# Main.net
KiCad netlist of a schematic drawn in Altium Designer
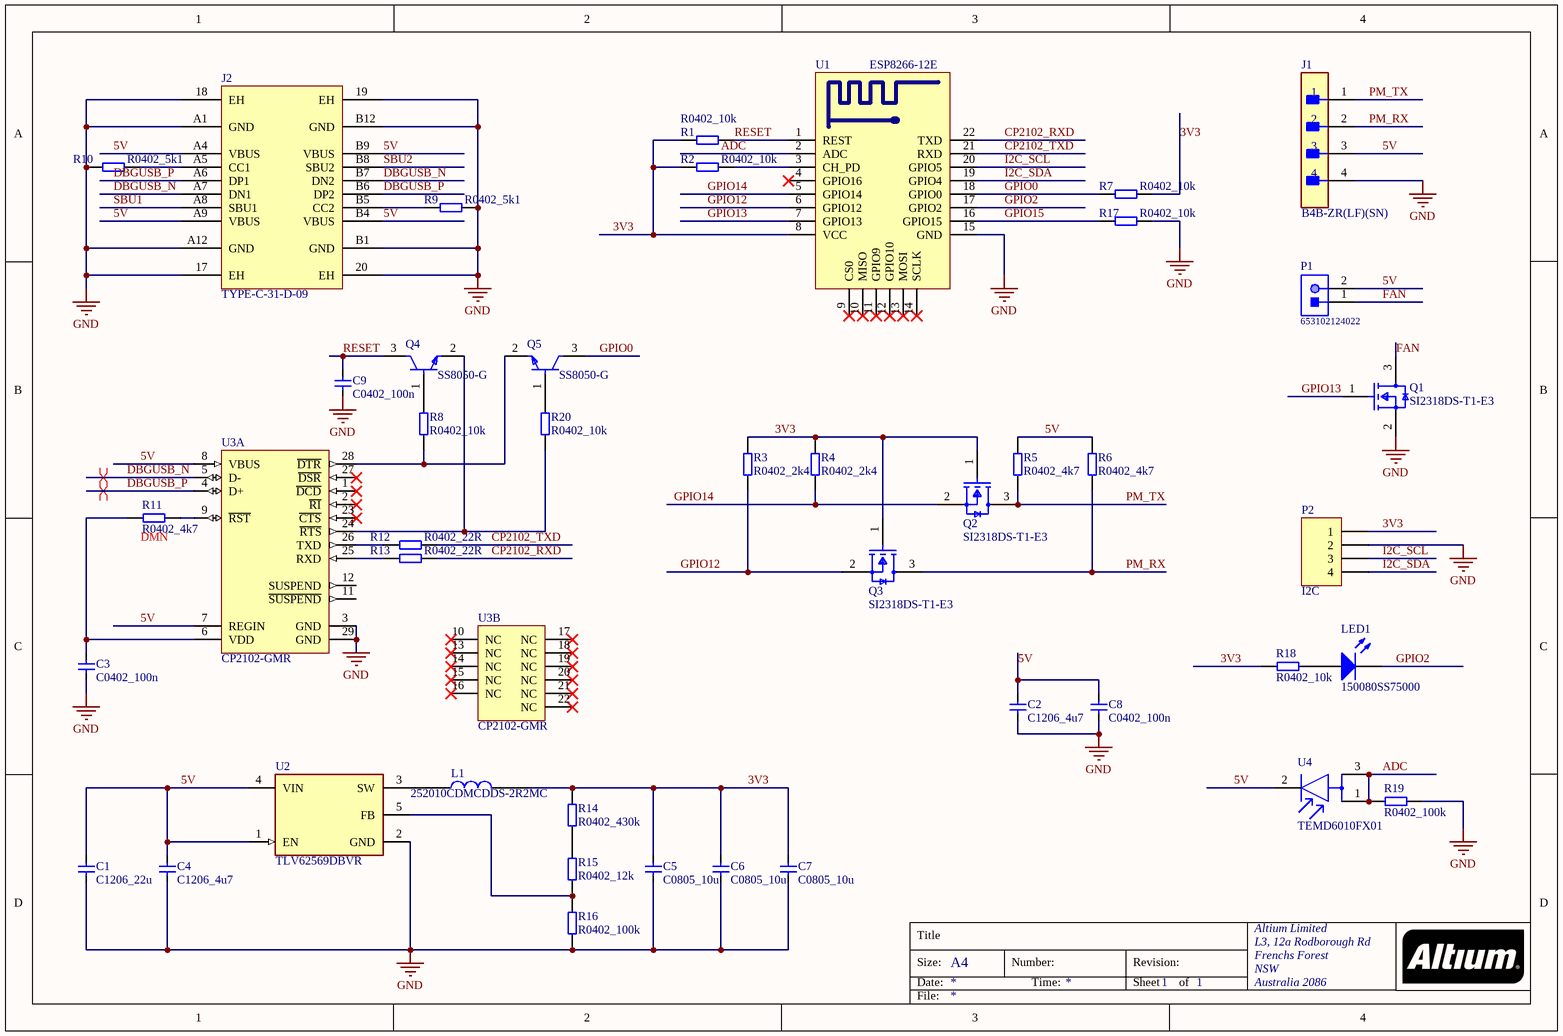
[diagram p0: Main.SchDoc]

(export (version "E")
  (design (tool "Eeschema 10.0.6"))
  (components
    (comp (ref "C1")
      (value "C1206_22u")
      (footprint "C1206")
      (fields (field (name "TOLERANCE") "0.2%"))
      (libsource (lib "NyaMoe Internal Altium Server") (part "Cap"))
    )
    (comp (ref "C2")
      (value "C1206_4u7")
      (footprint "C1206")
      (fields (field (name "TOLERANCE") "0.1%"))
      (libsource (lib "NyaMoe Internal Altium Server") (part "Cap"))
    )
    (comp (ref "C3")
      (value "C0402_100n")
      (footprint "C0402")
      (fields (field (name "TOLERANCE") "0.1%"))
      (libsource (lib "NyaMoe Internal Altium Server") (part "Cap"))
    )
    (comp (ref "C4")
      (value "C1206_4u7")
      (footprint "C1206")
      (fields (field (name "TOLERANCE") "0.1%"))
      (libsource (lib "NyaMoe Internal Altium Server") (part "Cap"))
    )
    (comp (ref "C5")
      (value "C0805_10u")
      (footprint "C0805")
      (description "C0805")
      (fields (field (name "TOLERANCE") "0.05%"))
      (libsource (lib "NyaMoe Internal Altium Server") (part "Cap"))
    )
    (comp (ref "C6")
      (value "C0805_10u")
      (footprint "C0805")
      (description "C0805")
      (fields (field (name "TOLERANCE") "0.05%"))
      (libsource (lib "NyaMoe Internal Altium Server") (part "Cap"))
    )
    (comp (ref "C7")
      (value "C0805_10u")
      (footprint "C0805")
      (description "C0805")
      (fields (field (name "TOLERANCE") "0.05%"))
      (libsource (lib "NyaMoe Internal Altium Server") (part "Cap"))
    )
    (comp (ref "C8")
      (value "C0402_100n")
      (footprint "C0402")
      (fields (field (name "TOLERANCE") "0.1%"))
      (libsource (lib "NyaMoe Internal Altium Server") (part "Cap"))
    )
    (comp (ref "C9")
      (value "C0402_100n")
      (footprint "C0402")
      (fields (field (name "TOLERANCE") "0.1%"))
      (libsource (lib "NyaMoe Internal Altium Server") (part "Cap"))
    )
    (comp (ref "J1")
      (value "B4B-ZR(LF)(SN)")
      (footprint "FP-B4B-ZR_LF_SN-MFG")
      (description "CONN HEADER VERT 4POS 1.5MM")
      (libsource (lib "Altium Content Vault") (part "299a8cea1bdcbc3624fe62c390fa72c"))
    )
    (comp (ref "J2")
      (value "TYPE-C-31-D-09")
      (footprint "New footprint 1")
      (libsource (lib "NyaMoe Internal Altium Server") (part "TYPE-C-31-D-09"))
    )
    (comp (ref "L1")
      (value "252010CDMCDDS-2R2MC")
      (footprint "INDC2520X10N")
      (description "Fixed Ind 2.2UH 2.5A 97 Mohm SMD")
      (libsource (lib "NyaMoe Internal Altium Server") (part "252010CDMCDDS-2R2MC"))
    )
    (comp (ref "LED1")
      (value "150080SS75000")
      (footprint "0805_A")
      (description "SMD mono-color Chip LED, WL-SMCW, Super Red")
      (fields (field (name "MANUFACTURER") "Wuerth Elektronik"))
      (libsource (lib "Altium Content Vault") (part "WE-LED_K1A2-2"))
    )
    (comp (ref "P1")
      (value "653102124022")
      (footprint "653102124022")
      (description "Male Shrouded Header WR-WTB, SMT, Vertical, pitch 1.25 mm, 1 x 2 position")
      (fields (field (name "MANUFACTURER") "Wurth Elektronik") (field (name "PUBLISHER") "WurthElektronik"))
      (libsource (lib "Altium Content Vault") (part "WE-CN-1P-M-R2"))
    )
    (comp (ref "P2")
      (value "I2C")
      (footprint "HDR1X4")
      (description "Header, 4-Pin")
      (fields (field (name "PUBLISHER") "Altium Limited"))
      (libsource (lib "Miscellaneous Connectors") (part "Header 4"))
    )
    (comp (ref "Q1")
      (value "SI2318DS-T1-E3")
      (footprint "FP-S-03946-MFG")
      (description "MOSFET N-CH 40V 3A SOT23-3")
      (fields
        (field (name "MANUFACTURER") "Vishay")
        (field (name "OCTOPART") "https://octopart.com/si2318ds-t1-e3-vishay-40866469")
      )
      (libsource (lib "Altium Content Vault") (part "3b9c635fedb024a5347a57b145af9cc"))
    )
    (comp (ref "Q2")
      (value "SI2318DS-T1-E3")
      (footprint "FP-S-03946-MFG")
      (description "MOSFET N-CH 40V 3A SOT23-3")
      (fields
        (field (name "MANUFACTURER") "Vishay")
        (field (name "OCTOPART") "https://octopart.com/si2318ds-t1-e3-vishay-40866469")
      )
      (libsource (lib "Altium Content Vault") (part "3b9c635fedb024a5347a57b145af9cc"))
    )
    (comp (ref "Q3")
      (value "SI2318DS-T1-E3")
      (footprint "FP-S-03946-MFG")
      (description "MOSFET N-CH 40V 3A SOT23-3")
      (fields
        (field (name "MANUFACTURER") "Vishay")
        (field (name "OCTOPART") "https://octopart.com/si2318ds-t1-e3-vishay-40866469")
      )
      (libsource (lib "Altium Content Vault") (part "3b9c635fedb024a5347a57b145af9cc"))
    )
    (comp (ref "Q4")
      (value "SS8050-G")
      (footprint "FP-SS8050-G-MFG")
      (description "NPN TRANSISTOR 1.5A 40V SOT-23 R")
      (libsource (lib "Altium Content Vault") (part "2a1388f82443b098dcd57d24ac7632d"))
    )
    (comp (ref "Q5")
      (value "SS8050-G")
      (footprint "FP-SS8050-G-MFG")
      (description "NPN TRANSISTOR 1.5A 40V SOT-23 R")
      (libsource (lib "Altium Content Vault") (part "2a1388f82443b098dcd57d24ac7632d"))
    )
    (comp (ref "R1")
      (value "R0402_10k")
      (footprint "R0402")
      (fields (field (name "TOLERANCE") "1%"))
      (libsource (lib "NyaMoe Internal Altium Server") (part "Res"))
    )
    (comp (ref "R2")
      (value "R0402_10k")
      (footprint "R0402")
      (fields (field (name "TOLERANCE") "1%"))
      (libsource (lib "NyaMoe Internal Altium Server") (part "Res"))
    )
    (comp (ref "R3")
      (value "R0402_2k4")
      (footprint "R0402")
      (fields (field (name "TOLERANCE") "1%"))
      (libsource (lib "NyaMoe Internal Altium Server") (part "Res"))
    )
    (comp (ref "R4")
      (value "R0402_2k4")
      (footprint "R0402")
      (fields (field (name "TOLERANCE") "1%"))
      (libsource (lib "NyaMoe Internal Altium Server") (part "Res"))
    )
    (comp (ref "R5")
      (value "R0402_4k7")
      (footprint "R0402")
      (fields (field (name "TOLERANCE") "1%"))
      (libsource (lib "NyaMoe Internal Altium Server") (part "Res"))
    )
    (comp (ref "R6")
      (value "R0402_4k7")
      (footprint "R0402")
      (fields (field (name "TOLERANCE") "1%"))
      (libsource (lib "NyaMoe Internal Altium Server") (part "Res"))
    )
    (comp (ref "R7")
      (value "R0402_10k")
      (footprint "R0402")
      (fields (field (name "TOLERANCE") "1%"))
      (libsource (lib "NyaMoe Internal Altium Server") (part "Res"))
    )
    (comp (ref "R8")
      (value "R0402_10k")
      (footprint "R0402")
      (fields (field (name "TOLERANCE") "1%"))
      (libsource (lib "NyaMoe Internal Altium Server") (part "Res"))
    )
    (comp (ref "R9")
      (value "R0402_5k1")
      (footprint "R0402")
      (fields (field (name "TOLERANCE") "1%"))
      (libsource (lib "NyaMoe Internal Altium Server") (part "Res"))
    )
    (comp (ref "R10")
      (value "R0402_5k1")
      (footprint "R0402")
      (fields (field (name "TOLERANCE") "1%"))
      (libsource (lib "NyaMoe Internal Altium Server") (part "Res"))
    )
    (comp (ref "R11")
      (value "R0402_4k7")
      (footprint "R0402")
      (fields (field (name "TOLERANCE") "1%"))
      (libsource (lib "NyaMoe Internal Altium Server") (part "Res"))
    )
    (comp (ref "R12")
      (value "R0402_22R")
      (footprint "R0402")
      (fields (field (name "TOLERANCE") "1%"))
      (libsource (lib "NyaMoe Internal Altium Server") (part "Res"))
    )
    (comp (ref "R13")
      (value "R0402_22R")
      (footprint "R0402")
      (fields (field (name "TOLERANCE") "1%"))
      (libsource (lib "NyaMoe Internal Altium Server") (part "Res"))
    )
    (comp (ref "R14")
      (value "R0402_430k")
      (footprint "R0402")
      (fields (field (name "TOLERANCE") "1%"))
      (libsource (lib "NyaMoe Internal Altium Server") (part "Res"))
    )
    (comp (ref "R15")
      (value "R0402_12k")
      (footprint "R0402")
      (fields (field (name "TOLERANCE") "1%"))
      (libsource (lib "NyaMoe Internal Altium Server") (part "Res"))
    )
    (comp (ref "R16")
      (value "R0402_100k")
      (footprint "R0402")
      (fields (field (name "TOLERANCE") "1%"))
      (libsource (lib "NyaMoe Internal Altium Server") (part "Res"))
    )
    (comp (ref "R17")
      (value "R0402_10k")
      (footprint "R0402")
      (fields (field (name "TOLERANCE") "1%"))
      (libsource (lib "NyaMoe Internal Altium Server") (part "Res"))
    )
    (comp (ref "R18")
      (value "R0402_10k")
      (footprint "R0402")
      (fields (field (name "TOLERANCE") "1%"))
      (libsource (lib "NyaMoe Internal Altium Server") (part "Res"))
    )
    (comp (ref "R19")
      (value "R0402_100k")
      (footprint "R0402")
      (fields (field (name "TOLERANCE") "1%"))
      (libsource (lib "NyaMoe Internal Altium Server") (part "Res"))
    )
    (comp (ref "R20")
      (value "R0402_10k")
      (footprint "R0402")
      (fields (field (name "TOLERANCE") "1%"))
      (libsource (lib "NyaMoe Internal Altium Server") (part "Res"))
    )
    (comp (ref "U1")
      (value "ESP8266-12E")
      (footprint "ESP_12E")
      (description "串口 WIFI模块，ESP-12E")
      (fields (field (name "版权归属") "源创客"))
      (libsource (lib "13.1 - 模块") (part "ESP8266-12E"))
    )
    (comp (ref "U2")
      (value "TLV62569DBVR")
      (footprint "FP-DBV0005A-MFG")
      (description "IC REG BUCK ADJ 2A SOT23-5")
      (libsource (lib "Altium Content Vault") (part "f8671745ee5fb9a493b385c735b730b"))
    )
    (comp (ref "U3")
      (value "CP2102-GMR")
      (footprint "SLAB-QFN-28-3125x3125TP_M")
      (description "Single-Chip USB to URAT Bridge, 3.3 V, -40 to 85 degC, 28-Pin QFN, RoHS, Tape and Reel")
      (fields (field (name "MANUFACTURER") "Silicon Labs"))
      (libsource (lib "Altium Content Vault") (part "SLAB-CP210X-QFN-28-29"))
    )
    (comp (ref "U4")
      (value "TEMD6010FX01")
      (footprint "FP-6_541-5080_01-4-MFG")
      (description "SENSOR PHOTODIODE 540NM SMD")
      (libsource (lib "Altium Content Vault") (part "efd04f4de317bbfa1bd732263da52e9"))
    )
  )
  (nets
    (net (code "1") (name "/3V3") (class "Default")
      (node (ref "C5") (pin "1") (pinfunction "1_1") (pintype "passive"))
      (node (ref "C6") (pin "1") (pinfunction "1_1") (pintype "passive"))
      (node (ref "C7") (pin "1") (pinfunction "1_1") (pintype "passive"))
      (node (ref "L1") (pin "2") (pinfunction "2_2") (pintype "passive"))
      (node (ref "P2") (pin "1") (pinfunction "1_1") (pintype "passive"))
      (node (ref "Q2") (pin "1") (pinfunction "G_1") (pintype "passive"))
      (node (ref "Q3") (pin "1") (pinfunction "G_1") (pintype "passive"))
      (node (ref "R1") (pin "1") (pinfunction "1_1") (pintype "passive"))
      (node (ref "R14") (pin "2") (pinfunction "2_2") (pintype "passive"))
      (node (ref "R18") (pin "1") (pinfunction "1_1") (pintype "passive"))
      (node (ref "R2") (pin "1") (pinfunction "1_1") (pintype "passive"))
      (node (ref "R3") (pin "2") (pinfunction "2_2") (pintype "passive"))
      (node (ref "R4") (pin "2") (pinfunction "2_2") (pintype "passive"))
      (node (ref "R7") (pin "2") (pinfunction "2_2") (pintype "passive"))
      (node (ref "U1") (pin "8") (pinfunction "VCC_8") (pintype "passive"))
    )
    (net (code "2") (name "/5V") (class "Default")
      (node (ref "C1") (pin "1") (pinfunction "1_1") (pintype "passive"))
      (node (ref "C2") (pin "1") (pinfunction "1_1") (pintype "passive"))
      (node (ref "C4") (pin "1") (pinfunction "1_1") (pintype "passive"))
      (node (ref "C8") (pin "1") (pinfunction "1_1") (pintype "passive"))
      (node (ref "J1") (pin "3") (pinfunction "3_3") (pintype "passive"))
      (node (ref "J2") (pin "A4") (pinfunction "VBUS_A4") (pintype "passive"))
      (node (ref "J2") (pin "A9") (pinfunction "VBUS_A9") (pintype "passive"))
      (node (ref "J2") (pin "B4") (pinfunction "VBUS_B4") (pintype "passive"))
      (node (ref "J2") (pin "B9") (pinfunction "VBUS_B9") (pintype "passive"))
      (node (ref "P1") (pin "2") (pinfunction "2_2") (pintype "passive"))
      (node (ref "R5") (pin "2") (pinfunction "2_2") (pintype "passive"))
      (node (ref "R6") (pin "2") (pinfunction "2_2") (pintype "passive"))
      (node (ref "U2") (pin "1") (pinfunction "EN_1") (pintype "input"))
      (node (ref "U2") (pin "4") (pinfunction "VIN_4") (pintype "power_in"))
      (node (ref "U3") (pin "7") (pinfunction "REGIN_7") (pintype "power_in"))
      (node (ref "U3") (pin "8") (pinfunction "VBUS_8") (pintype "input"))
      (node (ref "U4") (pin "2") (pinfunction "C_2") (pintype "passive"))
    )
    (net (code "3") (name "/ADC") (class "Default")
      (node (ref "R19") (pin "1") (pinfunction "1_1") (pintype "passive"))
      (node (ref "U1") (pin "2") (pinfunction "ADC_2") (pintype "passive"))
      (node (ref "U4") (pin "1") (pinfunction "A_1") (pintype "passive"))
      (node (ref "U4") (pin "3") (pinfunction "A_3") (pintype "passive"))
    )
    (net (code "4") (name "/CP2102_RXD") (class "Default")
      (node (ref "R13") (pin "2") (pinfunction "2_2") (pintype "passive"))
      (node (ref "U1") (pin "22") (pinfunction "TXD_22") (pintype "passive"))
    )
    (net (code "5") (name "/CP2102_TXD") (class "Default")
      (node (ref "R12") (pin "2") (pinfunction "2_2") (pintype "passive"))
      (node (ref "U1") (pin "21") (pinfunction "RXD_21") (pintype "passive"))
    )
    (net (code "6") (name "/DBGUSB_N") (class "Default")
      (node (ref "J2") (pin "A7") (pinfunction "DN1_A7") (pintype "passive"))
      (node (ref "J2") (pin "B7") (pinfunction "DN2_B7") (pintype "passive"))
      (node (ref "U3") (pin "5") (pinfunction "D-_5") (pintype "bidirectional"))
    )
    (net (code "7") (name "/DBGUSB_P") (class "Default")
      (node (ref "J2") (pin "A6") (pinfunction "DP1_A6") (pintype "passive"))
      (node (ref "J2") (pin "B6") (pinfunction "DP2_B6") (pintype "passive"))
      (node (ref "U3") (pin "4") (pinfunction "D+_4") (pintype "bidirectional"))
    )
    (net (code "8") (name "/FAN") (class "Default")
      (node (ref "P1") (pin "1") (pinfunction "1_1") (pintype "passive"))
      (node (ref "Q1") (pin "3") (pinfunction "D_3") (pintype "passive"))
    )
    (net (code "9") (name "/GPIO0") (class "Default")
      (node (ref "Q5") (pin "3") (pinfunction "C_3") (pintype "passive"))
      (node (ref "R7") (pin "1") (pinfunction "1_1") (pintype "passive"))
      (node (ref "U1") (pin "18") (pinfunction "GPIO0_18") (pintype "passive"))
    )
    (net (code "10") (name "/GPIO2") (class "Default")
      (node (ref "LED1") (pin "1") (pinfunction "K_1") (pintype "passive"))
      (node (ref "U1") (pin "17") (pinfunction "GPIO2_17") (pintype "passive"))
    )
    (net (code "11") (name "/GPIO12") (class "Default")
      (node (ref "Q3") (pin "2") (pinfunction "S_2") (pintype "passive"))
      (node (ref "R3") (pin "1") (pinfunction "1_1") (pintype "passive"))
      (node (ref "U1") (pin "6") (pinfunction "GPIO12_6") (pintype "passive"))
    )
    (net (code "12") (name "/GPIO13") (class "Default")
      (node (ref "Q1") (pin "1") (pinfunction "G_1") (pintype "passive"))
      (node (ref "U1") (pin "7") (pinfunction "GPIO13_7") (pintype "passive"))
    )
    (net (code "13") (name "/GPIO14") (class "Default")
      (node (ref "Q2") (pin "2") (pinfunction "S_2") (pintype "passive"))
      (node (ref "R4") (pin "1") (pinfunction "1_1") (pintype "passive"))
      (node (ref "U1") (pin "5") (pinfunction "GPIO14_5") (pintype "passive"))
    )
    (net (code "14") (name "/GPIO15") (class "Default")
      (node (ref "R17") (pin "1") (pinfunction "1_1") (pintype "passive"))
      (node (ref "U1") (pin "16") (pinfunction "GPIO15_16") (pintype "passive"))
    )
    (net (code "15") (name "/I2C_SCL") (class "Default")
      (node (ref "P2") (pin "3") (pinfunction "3_3") (pintype "passive"))
      (node (ref "U1") (pin "20") (pinfunction "GPIO5_20") (pintype "passive"))
    )
    (net (code "16") (name "/I2C_SDA") (class "Default")
      (node (ref "P2") (pin "4") (pinfunction "4_4") (pintype "passive"))
      (node (ref "U1") (pin "19") (pinfunction "GPIO4_19") (pintype "passive"))
    )
    (net (code "17") (name "/PM_RX") (class "Default")
      (node (ref "J1") (pin "2") (pinfunction "2_2") (pintype "passive"))
      (node (ref "Q3") (pin "3") (pinfunction "D_3") (pintype "passive"))
      (node (ref "R6") (pin "1") (pinfunction "1_1") (pintype "passive"))
    )
    (net (code "18") (name "/PM_TX") (class "Default")
      (node (ref "J1") (pin "1") (pinfunction "1_1") (pintype "passive"))
      (node (ref "Q2") (pin "3") (pinfunction "D_3") (pintype "passive"))
      (node (ref "R5") (pin "1") (pinfunction "1_1") (pintype "passive"))
    )
    (net (code "19") (name "/RESET") (class "Default")
      (node (ref "C9") (pin "1") (pinfunction "1_1") (pintype "passive"))
      (node (ref "Q4") (pin "3") (pinfunction "C_3") (pintype "passive"))
      (node (ref "R1") (pin "2") (pinfunction "2_2") (pintype "passive"))
      (node (ref "U1") (pin "1") (pinfunction "REST_1") (pintype "passive"))
    )
    (net (code "20") (name "/SBU1") (class "Default")
      (node (ref "J2") (pin "A8") (pinfunction "SBU1_A8") (pintype "passive"))
    )
    (net (code "21") (name "/SBU2") (class "Default")
      (node (ref "J2") (pin "B8") (pinfunction "SBU2_B8") (pintype "passive"))
    )
    (net (code "22") (name "GND") (class "Default")
      (node (ref "C1") (pin "2") (pinfunction "2_2") (pintype "passive"))
      (node (ref "C2") (pin "2") (pinfunction "2_2") (pintype "passive"))
      (node (ref "C3") (pin "2") (pinfunction "2_2") (pintype "passive"))
      (node (ref "C4") (pin "2") (pinfunction "2_2") (pintype "passive"))
      (node (ref "C5") (pin "2") (pinfunction "2_2") (pintype "passive"))
      (node (ref "C6") (pin "2") (pinfunction "2_2") (pintype "passive"))
      (node (ref "C7") (pin "2") (pinfunction "2_2") (pintype "passive"))
      (node (ref "C8") (pin "2") (pinfunction "2_2") (pintype "passive"))
      (node (ref "C9") (pin "2") (pinfunction "2_2") (pintype "passive"))
      (node (ref "J1") (pin "4") (pinfunction "4_4") (pintype "passive"))
      (node (ref "J2") (pin "17") (pinfunction "EH_17") (pintype "passive"))
      (node (ref "J2") (pin "18") (pinfunction "EH_18") (pintype "passive"))
      (node (ref "J2") (pin "19") (pinfunction "EH_19") (pintype "passive"))
      (node (ref "J2") (pin "20") (pinfunction "EH_20") (pintype "passive"))
      (node (ref "J2") (pin "A1") (pinfunction "GND_A1") (pintype "passive"))
      (node (ref "J2") (pin "A12") (pinfunction "GND_A12") (pintype "passive"))
      (node (ref "J2") (pin "B1") (pinfunction "GND_B1") (pintype "passive"))
      (node (ref "J2") (pin "B12") (pinfunction "GND_B12") (pintype "passive"))
      (node (ref "P2") (pin "2") (pinfunction "2_2") (pintype "passive"))
      (node (ref "Q1") (pin "2") (pinfunction "S_2") (pintype "passive"))
      (node (ref "R10") (pin "1") (pinfunction "1_1") (pintype "passive"))
      (node (ref "R16") (pin "1") (pinfunction "1_1") (pintype "passive"))
      (node (ref "R17") (pin "2") (pinfunction "2_2") (pintype "passive"))
      (node (ref "R19") (pin "2") (pinfunction "2_2") (pintype "passive"))
      (node (ref "R9") (pin "2") (pinfunction "2_2") (pintype "passive"))
      (node (ref "U1") (pin "15") (pinfunction "GND_15") (pintype "passive"))
      (node (ref "U2") (pin "2") (pinfunction "GND_2") (pintype "power_in"))
      (node (ref "U3") (pin "29") (pinfunction "GND_29") (pintype "power_in"))
      (node (ref "U3") (pin "3") (pinfunction "GND_3") (pintype "power_in"))
    )
    (net (code "23") (name "Net-(J2-CC1)") (class "Default")
      (node (ref "J2") (pin "A5") (pinfunction "CC1_A5") (pintype "passive"))
      (node (ref "R10") (pin "2") (pinfunction "2_2") (pintype "passive"))
    )
    (net (code "24") (name "Net-(J2-CC2)") (class "Default")
      (node (ref "J2") (pin "B5") (pinfunction "CC2_B5") (pintype "passive"))
      (node (ref "R9") (pin "1") (pinfunction "1_1") (pintype "passive"))
    )
    (net (code "25") (name "Net-(LED1-A)") (class "Default")
      (node (ref "LED1") (pin "2") (pinfunction "A_2") (pintype "passive"))
      (node (ref "R18") (pin "2") (pinfunction "2_2") (pintype "passive"))
    )
    (net (code "26") (name "Net-(Q4-B)") (class "Default")
      (node (ref "Q4") (pin "1") (pinfunction "B_1") (pintype "passive"))
      (node (ref "R8") (pin "2") (pinfunction "2_2") (pintype "passive"))
    )
    (net (code "27") (name "Net-(Q4-E)") (class "Default")
      (node (ref "Q4") (pin "2") (pinfunction "E_2") (pintype "passive"))
      (node (ref "R20") (pin "1") (pinfunction "1_1") (pintype "passive"))
      (node (ref "U3") (pin "24") (pinfunction "~{RTS}_24") (pintype "output"))
    )
    (net (code "28") (name "Net-(Q5-B)") (class "Default")
      (node (ref "Q5") (pin "1") (pinfunction "B_1") (pintype "passive"))
      (node (ref "R20") (pin "2") (pinfunction "2_2") (pintype "passive"))
    )
    (net (code "29") (name "Net-(Q5-E)") (class "Default")
      (node (ref "Q5") (pin "2") (pinfunction "E_2") (pintype "passive"))
      (node (ref "R8") (pin "1") (pinfunction "1_1") (pintype "passive"))
      (node (ref "U3") (pin "28") (pinfunction "~{DTR}_28") (pintype "output"))
    )
    (net (code "30") (name "Net-(R14-Pad1)") (class "Default")
      (node (ref "R14") (pin "1") (pinfunction "1_1") (pintype "passive"))
      (node (ref "R15") (pin "2") (pinfunction "2_2") (pintype "passive"))
    )
    (net (code "31") (name "Net-(U1-CH_PD)") (class "Default")
      (node (ref "R2") (pin "2") (pinfunction "2_2") (pintype "passive"))
      (node (ref "U1") (pin "3") (pinfunction "CH_PD_3") (pintype "passive"))
    )
    (net (code "32") (name "Net-(U2-FB)") (class "Default")
      (node (ref "R15") (pin "1") (pinfunction "1_1") (pintype "passive"))
      (node (ref "R16") (pin "2") (pinfunction "2_2") (pintype "passive"))
      (node (ref "U2") (pin "5") (pinfunction "FB_5") (pintype "passive"))
    )
    (net (code "33") (name "Net-(U2-SW)") (class "Default")
      (node (ref "L1") (pin "1") (pinfunction "1_1") (pintype "passive"))
      (node (ref "U2") (pin "3") (pinfunction "SW_3") (pintype "power_in"))
    )
    (net (code "34") (name "Net-(U3A-RXD)") (class "Default")
      (node (ref "R13") (pin "1") (pinfunction "1_1") (pintype "passive"))
      (node (ref "U3") (pin "25") (pinfunction "RXD_25") (pintype "input"))
    )
    (net (code "35") (name "Net-(U3A-TXD)") (class "Default")
      (node (ref "R12") (pin "1") (pinfunction "1_1") (pintype "passive"))
      (node (ref "U3") (pin "26") (pinfunction "TXD_26") (pintype "output"))
    )
    (net (code "36") (name "Net-(U3A-VDD)") (class "Default")
      (node (ref "C3") (pin "1") (pinfunction "1_1") (pintype "passive"))
      (node (ref "R11") (pin "1") (pinfunction "1_1") (pintype "passive"))
      (node (ref "U3") (pin "6") (pinfunction "VDD_6") (pintype "power_in"))
    )
    (net (code "37") (name "Net-(U3A-~{RST})") (class "Default")
      (node (ref "R11") (pin "2") (pinfunction "2_2") (pintype "passive"))
      (node (ref "U3") (pin "9") (pinfunction "~{RST}_9") (pintype "bidirectional"))
    )
    (net (code "38") (name "unconnected-(U1-CS0-Pad9)") (class "Default")
      (node (ref "U1") (pin "9") (pinfunction "CS0_9") (pintype "passive+no_connect"))
    )
    (net (code "39") (name "unconnected-(U1-GPIO9-Pad11)") (class "Default")
      (node (ref "U1") (pin "11") (pinfunction "GPIO9_11") (pintype "passive+no_connect"))
    )
    (net (code "40") (name "unconnected-(U1-GPIO10-Pad12)") (class "Default")
      (node (ref "U1") (pin "12") (pinfunction "GPIO10_12") (pintype "passive+no_connect"))
    )
    (net (code "41") (name "unconnected-(U1-GPIO16-Pad4)") (class "Default")
      (node (ref "U1") (pin "4") (pinfunction "GPIO16_4") (pintype "passive+no_connect"))
    )
    (net (code "42") (name "unconnected-(U1-MISO-Pad10)") (class "Default")
      (node (ref "U1") (pin "10") (pinfunction "MISO_10") (pintype "passive+no_connect"))
    )
    (net (code "43") (name "unconnected-(U1-MOSI-Pad13)") (class "Default")
      (node (ref "U1") (pin "13") (pinfunction "MOSI_13") (pintype "passive+no_connect"))
    )
    (net (code "44") (name "unconnected-(U1-SCLK-Pad14)") (class "Default")
      (node (ref "U1") (pin "14") (pinfunction "SCLK_14") (pintype "passive+no_connect"))
    )
    (net (code "45") (name "unconnected-(U3A-SUSPEND-Pad12)") (class "Default")
      (node (ref "U3") (pin "12") (pinfunction "SUSPEND_12") (pintype "output"))
    )
    (net (code "46") (name "unconnected-(U3A-~{CTS}-Pad23)") (class "Default")
      (node (ref "U3") (pin "23") (pinfunction "~{CTS}_23") (pintype "input+no_connect"))
    )
    (net (code "47") (name "unconnected-(U3A-~{DCD}-Pad1)") (class "Default")
      (node (ref "U3") (pin "1") (pinfunction "~{DCD}_1") (pintype "input+no_connect"))
    )
    (net (code "48") (name "unconnected-(U3A-~{DSR}-Pad27)") (class "Default")
      (node (ref "U3") (pin "27") (pinfunction "~{DSR}_27") (pintype "input+no_connect"))
    )
    (net (code "49") (name "unconnected-(U3A-~{RI}-Pad2)") (class "Default")
      (node (ref "U3") (pin "2") (pinfunction "~{RI}_2") (pintype "input+no_connect"))
    )
    (net (code "50") (name "unconnected-(U3A-~{SUSPEND}-Pad11)") (class "Default")
      (node (ref "U3") (pin "11") (pinfunction "~{SUSPEND}_11") (pintype "output"))
    )
    (net (code "51") (name "unconnected-(U3B-NC-Pad10)") (class "Default")
      (node (ref "U3") (pin "10") (pinfunction "NC_10") (pintype "passive+no_connect"))
    )
    (net (code "52") (name "unconnected-(U3B-NC-Pad13)") (class "Default")
      (node (ref "U3") (pin "13") (pinfunction "NC_13") (pintype "passive+no_connect"))
    )
    (net (code "53") (name "unconnected-(U3B-NC-Pad14)") (class "Default")
      (node (ref "U3") (pin "14") (pinfunction "NC_14") (pintype "passive+no_connect"))
    )
    (net (code "54") (name "unconnected-(U3B-NC-Pad15)") (class "Default")
      (node (ref "U3") (pin "15") (pinfunction "NC_15") (pintype "passive+no_connect"))
    )
    (net (code "55") (name "unconnected-(U3B-NC-Pad16)") (class "Default")
      (node (ref "U3") (pin "16") (pinfunction "NC_16") (pintype "passive+no_connect"))
    )
    (net (code "56") (name "unconnected-(U3B-NC-Pad17)") (class "Default")
      (node (ref "U3") (pin "17") (pinfunction "NC_17") (pintype "passive+no_connect"))
    )
    (net (code "57") (name "unconnected-(U3B-NC-Pad18)") (class "Default")
      (node (ref "U3") (pin "18") (pinfunction "NC_18") (pintype "passive+no_connect"))
    )
    (net (code "58") (name "unconnected-(U3B-NC-Pad19)") (class "Default")
      (node (ref "U3") (pin "19") (pinfunction "NC_19") (pintype "passive+no_connect"))
    )
    (net (code "59") (name "unconnected-(U3B-NC-Pad20)") (class "Default")
      (node (ref "U3") (pin "20") (pinfunction "NC_20") (pintype "passive+no_connect"))
    )
    (net (code "60") (name "unconnected-(U3B-NC-Pad21)") (class "Default")
      (node (ref "U3") (pin "21") (pinfunction "NC_21") (pintype "passive+no_connect"))
    )
    (net (code "61") (name "unconnected-(U3B-NC-Pad22)") (class "Default")
      (node (ref "U3") (pin "22") (pinfunction "NC_22") (pintype "passive+no_connect"))
    )
  )
)
